# Alim.net
KiCad netlist of a schematic drawn in Altium Designer
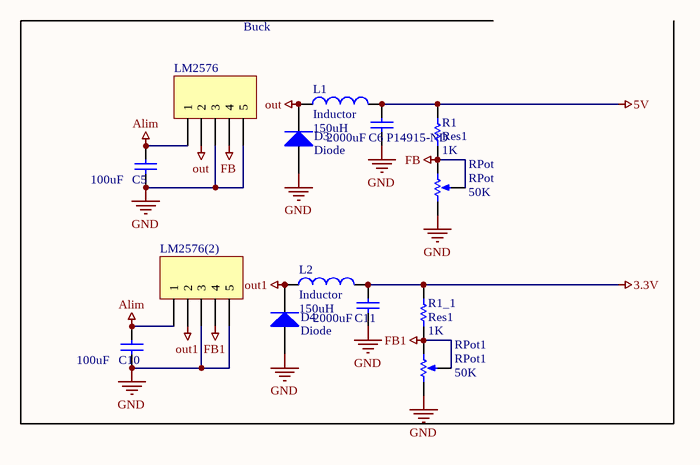
[diagram p0: Alim.SchDoc]

(export (version "E")
  (design (tool "Eeschema 10.0.6"))
  (components
    (comp (ref "C5")
      (value "100uF")
      (footprint "condo_alim1:Condo alim 1")
      (description "Capacitor (Semiconductor SIM Model)")
      (fields (field (name "Comment") "Cap Semi") (field (name "PUBLISHER") "Altium Limited"))
      (libsource (lib "Miscellaneous Devices - Copy") (part "Cap Semi"))
    )
    (comp (ref "C6 P14915-ND")
      (value "2000uF")
      (footprint "Capacité:Capacité alim 2")
      (description "Capacitor (Semiconductor SIM Model)")
      (fields (field (name "Comment") "Cap Semi") (field (name "PUBLISHER") "Altium Limited"))
      (libsource (lib "Miscellaneous Devices - Copy") (part "Cap Semi"))
    )
    (comp (ref "C10")
      (value "100uF")
      (footprint "condo_alim1:Condo alim 1")
      (description "Capacitor (Semiconductor SIM Model)")
      (fields (field (name "Comment") "Cap Semi") (field (name "PUBLISHER") "Altium Limited"))
      (libsource (lib "Miscellaneous Devices - Copy") (part "Cap Semi"))
    )
    (comp (ref "C11")
      (value "2000uF")
      (footprint "Capacité:Capacité alim 2")
      (description "Capacitor (Semiconductor SIM Model)")
      (fields (field (name "Comment") "Cap Semi") (field (name "PUBLISHER") "Altium Limited"))
      (libsource (lib "Miscellaneous Devices - Copy") (part "Cap Semi"))
    )
    (comp (ref "D3")
      (value "Diode")
      (footprint "Fuse1A:Diode alim")
      (description "Default Diode")
      (fields (field (name "PUBLISHER") "Altium Limited"))
      (libsource (lib "Miscellaneous Devices") (part "Diode"))
    )
    (comp (ref "D4")
      (value "Diode")
      (footprint "Fuse1A:Diode alim")
      (description "Default Diode")
      (fields (field (name "PUBLISHER") "Altium Limited"))
      (libsource (lib "Miscellaneous Devices") (part "Diode"))
    )
    (comp (ref "L1")
      (value "Inductor")
      (footprint "Capacité:Inductance alim")
      (fields (field (name "ALTIUM_VALUE") "150uH") (field (name "PUBLISHER") "Altium Limited"))
      (libsource (lib "Miscellaneous Devices") (part "Inductor"))
    )
    (comp (ref "L2")
      (value "Inductor")
      (footprint "Capacité:Inductance alim")
      (fields (field (name "ALTIUM_VALUE") "150uH") (field (name "PUBLISHER") "Altium Limited"))
      (libsource (lib "Miscellaneous Devices") (part "Inductor"))
    )
    (comp (ref "LM2576")
      (value "Header 5H")
      (footprint "LM276:LM276")
      (description "Header, 5-Pin, Right Angle")
      (fields (field (name "PUBLISHER") "Altium Limited"))
      (libsource (lib "Miscellaneous Connectors") (part "Header 5H"))
    )
    (comp (ref "LM2576(2)")
      (value "Header 5H")
      (footprint "LM276:LM276")
      (description "Header, 5-Pin, Right Angle")
      (fields (field (name "PUBLISHER") "Altium Limited"))
      (libsource (lib "Miscellaneous Connectors") (part "Header 5H"))
    )
    (comp (ref "R1")
      (value "Res1")
      (footprint "Resistance:470  and 4.7k Resistance")
      (description "Resistor")
      (fields (field (name "ALTIUM_VALUE") "1K") (field (name "PUBLISHER") "Altium Limited"))
      (libsource (lib "Miscellaneous Devices") (part "Res1"))
    )
    (comp (ref "R1_1")
      (value "Res1")
      (footprint "Resistance:470  and 4.7k Resistance")
      (description "Resistor")
      (fields (field (name "ALTIUM_VALUE") "1K") (field (name "PUBLISHER") "Altium Limited"))
      (libsource (lib "Miscellaneous Devices") (part "Res1"))
    )
    (comp (ref "RPot")
      (value "RPot")
      (footprint "Resistance:Potentionmètre 50k")
      (description "Potentiometer")
      (fields (field (name "ALTIUM_VALUE") "50K") (field (name "PUBLISHER") "Altium Limited"))
      (libsource (lib "") (part "RPot_1"))
    )
    (comp (ref "RPot1")
      (value "RPot1")
      (footprint "Resistance:Potentionmètre 50k")
      (description "Potentiometer")
      (fields (field (name "ALTIUM_VALUE") "50K") (field (name "PUBLISHER") "Altium Limited"))
      (libsource (lib "Miscellaneous Devices") (part "RPot"))
    )
  )
  (nets
    (net (code "1") (name "3.3V") (class "Default")
      (node (ref "C11") (pin "2") (pinfunction "2_2") (pintype "passive"))
      (node (ref "L2") (pin "2") (pinfunction "2_2") (pintype "passive"))
      (node (ref "R1_1") (pin "1") (pinfunction "1_1") (pintype "passive"))
    )
    (net (code "2") (name "5V") (class "Default")
      (node (ref "C6 P14915-ND") (pin "2") (pinfunction "2_2") (pintype "passive"))
      (node (ref "L1") (pin "2") (pinfunction "2_2") (pintype "passive"))
      (node (ref "R1") (pin "1") (pinfunction "1_1") (pintype "passive"))
    )
    (net (code "3") (name "Alim") (class "Default")
      (node (ref "C10") (pin "2") (pinfunction "2_2") (pintype "passive"))
      (node (ref "C5") (pin "2") (pinfunction "2_2") (pintype "passive"))
      (node (ref "LM2576") (pin "1") (pinfunction "1_1") (pintype "passive"))
      (node (ref "LM2576(2)") (pin "1") (pinfunction "1_1") (pintype "passive"))
    )
    (net (code "4") (name "FB") (class "Default")
      (node (ref "LM2576") (pin "4") (pinfunction "4_4") (pintype "passive"))
      (node (ref "R1") (pin "2") (pinfunction "2_2") (pintype "passive"))
      (node (ref "RPot") (pin "2") (pinfunction "BOT_2") (pintype "passive"))
      (node (ref "RPot") (pin "3") (pinfunction "TAP_3") (pintype "passive"))
    )
    (net (code "5") (name "FB1") (class "Default")
      (node (ref "LM2576(2)") (pin "4") (pinfunction "4_4") (pintype "passive"))
      (node (ref "R1_1") (pin "2") (pinfunction "2_2") (pintype "passive"))
      (node (ref "RPot1") (pin "2") (pinfunction "TAP_2") (pintype "passive"))
      (node (ref "RPot1") (pin "3") (pinfunction "BOT_3") (pintype "passive"))
    )
    (net (code "6") (name "GND") (class "Default")
      (node (ref "C10") (pin "1") (pinfunction "1_1") (pintype "passive"))
      (node (ref "C11") (pin "1") (pinfunction "1_1") (pintype "passive"))
      (node (ref "C5") (pin "1") (pinfunction "1_1") (pintype "passive"))
      (node (ref "C6 P14915-ND") (pin "1") (pinfunction "1_1") (pintype "passive"))
      (node (ref "D3") (pin "1") (pinfunction "A_1") (pintype "passive"))
      (node (ref "D4") (pin "1") (pinfunction "A_1") (pintype "passive"))
      (node (ref "LM2576") (pin "3") (pinfunction "3_3") (pintype "passive"))
      (node (ref "LM2576") (pin "5") (pinfunction "5_5") (pintype "passive"))
      (node (ref "LM2576(2)") (pin "3") (pinfunction "3_3") (pintype "passive"))
      (node (ref "LM2576(2)") (pin "5") (pinfunction "5_5") (pintype "passive"))
      (node (ref "RPot") (pin "1") (pinfunction "TOP_1") (pintype "passive"))
      (node (ref "RPot1") (pin "1") (pinfunction "TOP_1") (pintype "passive"))
    )
    (net (code "7") (name "out") (class "Default")
      (node (ref "D3") (pin "2") (pinfunction "K_2") (pintype "passive"))
      (node (ref "L1") (pin "1") (pinfunction "1_1") (pintype "passive"))
      (node (ref "LM2576") (pin "2") (pinfunction "2_2") (pintype "passive"))
    )
    (net (code "8") (name "out1") (class "Default")
      (node (ref "D4") (pin "2") (pinfunction "K_2") (pintype "passive"))
      (node (ref "L2") (pin "1") (pinfunction "1_1") (pintype "passive"))
      (node (ref "LM2576(2)") (pin "2") (pinfunction "2_2") (pintype "passive"))
    )
  )
)
